# RTLS_Node_sch.net
KiCad netlist of a schematic drawn in Altium Designer
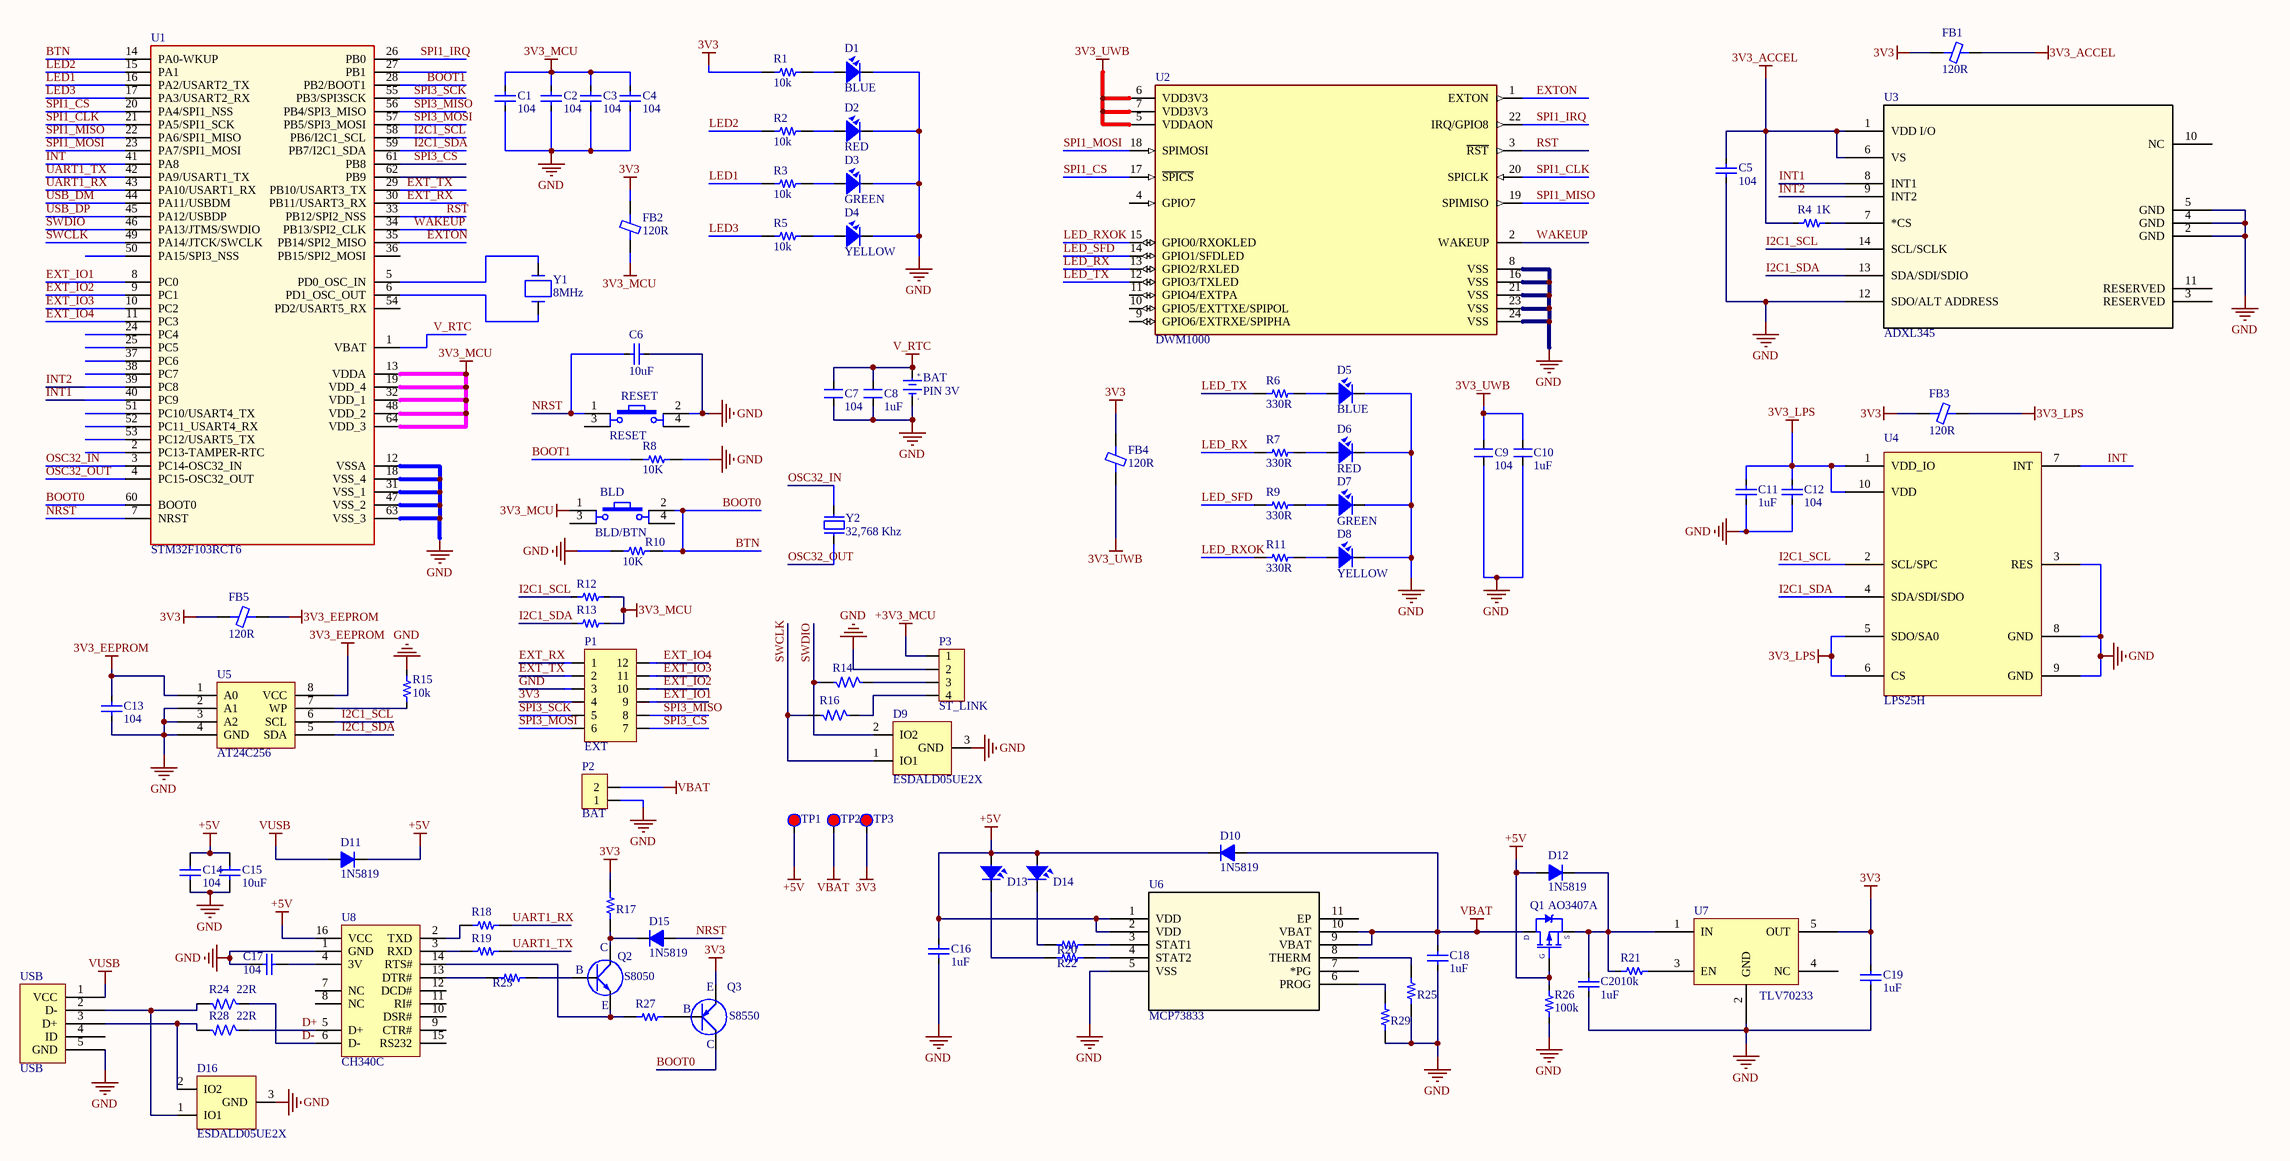
[diagram p0: RTLS_Node_sch.SchDoc]

(export (version "E")
  (design (tool "Eeschema 10.0.6"))
  (components
    (comp (ref "BAT")
      (value "PIN 3V")
      (footprint "CR1220 SMD")
      (description "Battery 3VDC")
      (libsource (lib "My Library") (part "PIN 3V"))
    )
    (comp (ref "BLD")
      (value "BLD/BTN")
      (footprint "SW4 - SMD")
      (description "Switch button 4 pin")
      (libsource (lib "My Library") (part "SW4"))
    )
    (comp (ref "C1")
      (value "104")
      (footprint "CAP_0603")
      (description "Capacitor")
      (fields (field (name "PUBLISHER") "Altium Limited"))
      (libsource (lib "") (part "CapSMD_1"))
    )
    (comp (ref "C2")
      (value "104")
      (footprint "CAP_0603")
      (description "Capacitor")
      (fields (field (name "PUBLISHER") "Altium Limited"))
      (libsource (lib "") (part "CapSMD_1"))
    )
    (comp (ref "C3")
      (value "104")
      (footprint "CAP_0603")
      (description "Capacitor")
      (fields (field (name "PUBLISHER") "Altium Limited"))
      (libsource (lib "") (part "CapSMD_1"))
    )
    (comp (ref "C4")
      (value "104")
      (footprint "CAP_0603")
      (description "Capacitor")
      (fields (field (name "PUBLISHER") "Altium Limited"))
      (libsource (lib "") (part "CapSMD_1"))
    )
    (comp (ref "C5")
      (value "104")
      (footprint "CAP_0603")
      (description "Capacitor")
      (fields (field (name "PUBLISHER") "Altium Limited"))
      (libsource (lib "") (part "CapSMD_1"))
    )
    (comp (ref "C6")
      (value "10uF")
      (footprint "CAP_0603")
      (description "Capacitor")
      (fields (field (name "PUBLISHER") "Altium Limited"))
      (libsource (lib "") (part "CapSMD_1"))
    )
    (comp (ref "C7")
      (value "104")
      (footprint "CAP_0603")
      (description "Cap SMD")
      (libsource (lib "GPS_Traking_V1_1") (part "CM"))
    )
    (comp (ref "C8")
      (value "1uF")
      (footprint "CAP_0603")
      (description "Cap SMD")
      (libsource (lib "GPS_Traking_V1_1") (part "CM"))
    )
    (comp (ref "C9")
      (value "104")
      (footprint "CAP_0603")
      (description "Cap SMD")
      (libsource (lib "GPS_Traking_V1_1") (part "CM"))
    )
    (comp (ref "C10")
      (value "1uF")
      (footprint "CAP_0603")
      (description "Cap SMD")
      (libsource (lib "GPS_Traking_V1_1") (part "CM"))
    )
    (comp (ref "C11")
      (value "1uF")
      (footprint "CAP_0603")
      (description "Capacitor")
      (fields (field (name "PUBLISHER") "Altium Limited"))
      (libsource (lib "") (part "CapSMD_1"))
    )
    (comp (ref "C12")
      (value "104")
      (footprint "CAP_0603")
      (description "Capacitor")
      (fields (field (name "PUBLISHER") "Altium Limited"))
      (libsource (lib "") (part "CapSMD_1"))
    )
    (comp (ref "C13")
      (value "104")
      (footprint "CAP_0603")
      (description "Capacitor")
      (fields (field (name "PUBLISHER") "Altium Limited"))
      (libsource (lib "") (part "CapSMD_1"))
    )
    (comp (ref "C14")
      (value "104")
      (footprint "CAP_0603")
      (description "Capacitor")
      (fields (field (name "PUBLISHER") "Altium Limited"))
      (libsource (lib "My Library") (part "CapSMD"))
    )
    (comp (ref "C15")
      (value "10uF")
      (footprint "CAP_0603")
      (description "Capacitor")
      (fields (field (name "PUBLISHER") "Altium Limited"))
      (libsource (lib "My Library") (part "CapSMD"))
    )
    (comp (ref "C16")
      (value "1uF")
      (footprint "CAP_0603")
      (description "Capacitor")
      (fields (field (name "PUBLISHER") "Altium Limited"))
      (libsource (lib "") (part "CapSMD_1"))
    )
    (comp (ref "C17")
      (value "104")
      (footprint "CAP_0603")
      (description "Capacitor")
      (fields (field (name "PUBLISHER") "Altium Limited"))
      (libsource (lib "My Library") (part "CapSMD"))
    )
    (comp (ref "C18")
      (value "1uF")
      (footprint "CAP_0603")
      (description "Capacitor")
      (fields (field (name "PUBLISHER") "Altium Limited"))
      (libsource (lib "") (part "CapSMD_1"))
    )
    (comp (ref "C19")
      (value "1uF")
      (footprint "CAP_0603")
      (description "Capacitor")
      (fields (field (name "PUBLISHER") "Altium Limited"))
      (libsource (lib "") (part "CapSMD_1"))
    )
    (comp (ref "C20")
      (value "1uF")
      (footprint "CAP_0603")
      (description "Capacitor")
      (fields (field (name "PUBLISHER") "Altium Limited"))
      (libsource (lib "") (part "CapSMD_1"))
    )
    (comp (ref "D1")
      (value "BLUE")
      (footprint "LED-0603-Red")
      (description "LED Single colour Green and Red")
      (libsource (lib "My Library") (part "LED"))
    )
    (comp (ref "D2")
      (value "RED")
      (footprint "LED-0603-Red")
      (description "LED Single colour Green and Red")
      (libsource (lib "My Library") (part "LED"))
    )
    (comp (ref "D3")
      (value "GREEN")
      (footprint "LED-0603-Green")
      (description "LED Single colour Green and Red")
      (libsource (lib "My Library") (part "LED"))
    )
    (comp (ref "D4")
      (value "YELLOW")
      (footprint "LED-0603-Red")
      (description "LED Single colour Green and Red")
      (libsource (lib "My Library") (part "LED"))
    )
    (comp (ref "D5")
      (value "BLUE")
      (footprint "LED-0603-Green")
      (description "LED Single colour Green and Red")
      (libsource (lib "My Library") (part "LED"))
    )
    (comp (ref "D6")
      (value "RED")
      (footprint "LED-0603-Red")
      (description "LED Single colour Green and Red")
      (libsource (lib "My Library") (part "LED"))
    )
    (comp (ref "D7")
      (value "GREEN")
      (footprint "LED-0603-Green")
      (description "LED Single colour Green and Red")
      (libsource (lib "My Library") (part "LED"))
    )
    (comp (ref "D8")
      (value "YELLOW")
      (footprint "LED-0603-Green")
      (description "LED Single colour Green and Red")
      (libsource (lib "My Library") (part "LED"))
    )
    (comp (ref "D9")
      (value "ESDALD05UE2X")
      (footprint "SOT23")
      (libsource (lib "My Library") (part "ESDALD05UE2X"))
    )
    (comp (ref "D10")
      (value "1N5819")
      (footprint "SOD-123")
      (description "Diode 1A")
      (libsource (lib "GPS_Traking_V1_1") (part "D1A_1"))
    )
    (comp (ref "D11")
      (value "1N5819")
      (footprint "SOD-123")
      (description "Diode 1A")
      (libsource (lib "GPS_Traking_V1_1") (part "D1A_1"))
    )
    (comp (ref "D12")
      (value "1N5819")
      (footprint "SOD-123")
      (description "Diode 1A")
      (libsource (lib "GPS_Traking_V1_1") (part "D1A_1"))
    )
    (comp (ref "D13")
      (value "YELLOW")
      (footprint "LED-0603-Red")
      (description "LED Single colour Green and Red")
      (libsource (lib "My Library") (part "LED"))
    )
    (comp (ref "D14")
      (value "YELLOW")
      (footprint "LED-0603-Green")
      (description "LED Single colour Green and Red")
      (libsource (lib "My Library") (part "LED"))
    )
    (comp (ref "D15")
      (value "1N5819")
      (footprint "SOD-123")
      (description "Diode 1A")
      (libsource (lib "GPS_Traking_V1_1") (part "D1A_1"))
    )
    (comp (ref "D16")
      (value "ESDALD05UE2X")
      (footprint "SOT23")
      (libsource (lib "My Library") (part "ESDALD05UE2X"))
    )
    (comp (ref "FB1")
      (value "120R")
      (footprint "RES-SMD-0603")
      (description "Ferrite beads")
      (libsource (lib "My Library") (part "Ferrite beads"))
    )
    (comp (ref "FB2")
      (value "120R")
      (footprint "RES-SMD-0603")
      (description "Ferrite beads")
      (libsource (lib "My Library") (part "Ferrite beads"))
    )
    (comp (ref "FB3")
      (value "120R")
      (footprint "RES-SMD-0603")
      (description "Ferrite beads")
      (libsource (lib "My Library") (part "Ferrite beads"))
    )
    (comp (ref "FB4")
      (value "120R")
      (footprint "RES-SMD-0603")
      (description "Ferrite beads")
      (libsource (lib "My Library") (part "Ferrite beads"))
    )
    (comp (ref "FB5")
      (value "120R")
      (footprint "RES-SMD-0603")
      (description "Ferrite beads")
      (libsource (lib "My Library") (part "Ferrite beads"))
    )
    (comp (ref "P1")
      (value "EXT")
      (footprint "JP6-C2T")
      (description "WR-PHD 2.54 mm Dual Socket Header")
      (fields
        (field (name "MANUFACTURER") "Würth Elektronik eiSos GmbH")
        (field (name "PARTNO") "61301221821")
        (field (name "CREATED BY") "Karrer Zheng")
      )
      (libsource (lib "My Library") (part "JP6x2"))
    )
    (comp (ref "P2")
      (value "BAT")
      (footprint "HEAD2P-1.25")
      (description "Header IDC, 2 x 1 Pin Vertical 2.54mm Pitch (Non-Boxed, Male)")
      (fields
        (field (name "MANUFACTURER") "Würth Elektronik eiSos GmbH")
        (field (name "PARTNO") "613002143121")
        (field (name "CREATED BY") "Karrer Zheng")
      )
      (libsource (lib "My Library") (part "Header2"))
    )
    (comp (ref "P3")
      (value "ST_LINK")
      (footprint "HEADER4P-1.25")
      (description "Header IDC, 4 x 1 Pin Vertical 2.54mm Pitch (Non-Boxed, Male)")
      (fields
        (field (name "MANUFACTURER") "Würth Elektronik eiSos GmbH")
        (field (name "PARTNO") "613002143121")
        (field (name "CREATED BY") "Karrer Zheng")
      )
      (libsource (lib "My Library") (part "Header4"))
    )
    (comp (ref "Q1") (value "AO3407A") (footprint "AO3407A") (libsource (lib "My Library") (part "AO3407A")))
    (comp (ref "Q2") (value "S8050") (footprint "SOT23") (libsource (lib "My Library") (part "S8050")))
    (comp (ref "Q3") (value "S8550") (footprint "SOT23") (libsource (lib "My Library") (part "S8550")))
    (comp (ref "R1")
      (value "10k")
      (footprint "RES-SMD-0603")
      (description "Resistor")
      (fields
        (field (name "MANUFACTURER") "Generic Components")
        (field (name "PUBLISHER") "Altium Hobart Technology Centre")
      )
      (libsource (lib "My Library") (part "Resistor - SMD"))
    )
    (comp (ref "R2")
      (value "10k")
      (footprint "RES-SMD-0603")
      (description "Resistor")
      (fields
        (field (name "MANUFACTURER") "Generic Components")
        (field (name "PUBLISHER") "Altium Hobart Technology Centre")
      )
      (libsource (lib "My Library") (part "Resistor - SMD"))
    )
    (comp (ref "R3")
      (value "10k")
      (footprint "RES-SMD-0603")
      (description "Resistor")
      (fields
        (field (name "MANUFACTURER") "Generic Components")
        (field (name "PUBLISHER") "Altium Hobart Technology Centre")
      )
      (libsource (lib "My Library") (part "Resistor - SMD"))
    )
    (comp (ref "R4")
      (value "1K")
      (footprint "RES-SMD-0603")
      (description "Resistor")
      (fields
        (field (name "MANUFACTURER") "Generic Components")
        (field (name "PUBLISHER") "Altium Hobart Technology Centre")
      )
      (libsource (lib "") (part "Resistor - SMD_1"))
    )
    (comp (ref "R5")
      (value "10k")
      (footprint "RES-SMD-0603")
      (description "Resistor")
      (fields
        (field (name "MANUFACTURER") "Generic Components")
        (field (name "PUBLISHER") "Altium Hobart Technology Centre")
      )
      (libsource (lib "My Library") (part "Resistor - SMD"))
    )
    (comp (ref "R6")
      (value "330R")
      (footprint "RES-SMD-0603")
      (description "Resistor")
      (fields
        (field (name "MANUFACTURER") "Generic Components")
        (field (name "PUBLISHER") "Altium Hobart Technology Centre")
      )
      (libsource (lib "My Library") (part "Resistor - SMD"))
    )
    (comp (ref "R7")
      (value "330R")
      (footprint "RES-SMD-0603")
      (description "Resistor")
      (fields
        (field (name "MANUFACTURER") "Generic Components")
        (field (name "PUBLISHER") "Altium Hobart Technology Centre")
      )
      (libsource (lib "My Library") (part "Resistor - SMD"))
    )
    (comp (ref "R8")
      (value "10K")
      (footprint "RES-SMD-0603")
      (description "Resistor")
      (fields
        (field (name "MANUFACTURER") "Generic Components")
        (field (name "PUBLISHER") "Altium Hobart Technology Centre")
      )
      (libsource (lib "My Library") (part "Resistor - SMD"))
    )
    (comp (ref "R9")
      (value "330R")
      (footprint "RES-SMD-0603")
      (description "Resistor")
      (fields
        (field (name "MANUFACTURER") "Generic Components")
        (field (name "PUBLISHER") "Altium Hobart Technology Centre")
      )
      (libsource (lib "My Library") (part "Resistor - SMD"))
    )
    (comp (ref "R10")
      (value "10K")
      (footprint "RES-SMD-0603")
      (description "Resistor")
      (fields
        (field (name "MANUFACTURER") "Generic Components")
        (field (name "PUBLISHER") "Altium Hobart Technology Centre")
      )
      (libsource (lib "My Library") (part "Resistor - SMD"))
    )
    (comp (ref "R11")
      (value "330R")
      (footprint "RES-SMD-0603")
      (description "Resistor")
      (fields
        (field (name "MANUFACTURER") "Generic Components")
        (field (name "PUBLISHER") "Altium Hobart Technology Centre")
      )
      (libsource (lib "My Library") (part "Resistor - SMD"))
    )
    (comp (ref "R12")
      (value "4.7k")
      (footprint "RES-SMD-0603")
      (description "Resistor")
      (fields
        (field (name "MANUFACTURER") "Generic Components")
        (field (name "PUBLISHER") "Altium Hobart Technology Centre")
      )
      (libsource (lib "") (part "Resistor - SMD_1"))
    )
    (comp (ref "R13")
      (value "4.7k")
      (footprint "RES-SMD-0603")
      (description "Resistor")
      (fields
        (field (name "MANUFACTURER") "Generic Components")
        (field (name "PUBLISHER") "Altium Hobart Technology Centre")
      )
      (libsource (lib "") (part "Resistor - SMD_1"))
    )
    (comp (ref "R14")
      (value "10R")
      (footprint "RES-SMD-0603")
      (description "Resistor SMD")
      (libsource (lib "GPS_Traking_V1_1") (part "RM"))
    )
    (comp (ref "R15")
      (value "10k")
      (footprint "RES-SMD-0603")
      (description "Resistor")
      (fields
        (field (name "MANUFACTURER") "Generic Components")
        (field (name "PUBLISHER") "Altium Hobart Technology Centre")
      )
      (libsource (lib "") (part "Resistor - SMD_1"))
    )
    (comp (ref "R16")
      (value "10R")
      (footprint "RES-SMD-0603")
      (description "Resistor SMD")
      (libsource (lib "GPS_Traking_V1_1") (part "RM"))
    )
    (comp (ref "R17")
      (value "1K")
      (footprint "RES-SMD-0603")
      (description "Resistor")
      (fields
        (field (name "MANUFACTURER") "Generic Components")
        (field (name "PUBLISHER") "Altium Hobart Technology Centre")
      )
      (libsource (lib "My Library") (part "Resistor - SMD"))
    )
    (comp (ref "R18")
      (value "1K")
      (footprint "RES-SMD-0603")
      (description "Resistor")
      (fields
        (field (name "MANUFACTURER") "Generic Components")
        (field (name "PUBLISHER") "Altium Hobart Technology Centre")
      )
      (libsource (lib "My Library") (part "Resistor - SMD"))
    )
    (comp (ref "R19")
      (value "1K")
      (footprint "RES-SMD-0603")
      (description "Resistor")
      (fields
        (field (name "MANUFACTURER") "Generic Components")
        (field (name "PUBLISHER") "Altium Hobart Technology Centre")
      )
      (libsource (lib "My Library") (part "Resistor - SMD"))
    )
    (comp (ref "R20")
      (value "10k")
      (footprint "RES-SMD-0603")
      (description "Resistor")
      (fields
        (field (name "MANUFACTURER") "Generic Components")
        (field (name "PUBLISHER") "Altium Hobart Technology Centre")
      )
      (libsource (lib "My Library") (part "Resistor - SMD"))
    )
    (comp (ref "R21")
      (value "10k")
      (footprint "RES-SMD-0603")
      (description "Resistor")
      (fields
        (field (name "MANUFACTURER") "Generic Components")
        (field (name "PUBLISHER") "Altium Hobart Technology Centre")
      )
      (libsource (lib "") (part "Resistor - SMD_1"))
    )
    (comp (ref "R22")
      (value "10k")
      (footprint "RES-SMD-0603")
      (description "Resistor")
      (fields
        (field (name "MANUFACTURER") "Generic Components")
        (field (name "PUBLISHER") "Altium Hobart Technology Centre")
      )
      (libsource (lib "My Library") (part "Resistor - SMD"))
    )
    (comp (ref "R23")
      (value "1K")
      (footprint "RES-SMD-0603")
      (description "Resistor")
      (fields
        (field (name "MANUFACTURER") "Generic Components")
        (field (name "PUBLISHER") "Altium Hobart Technology Centre")
      )
      (libsource (lib "My Library") (part "Resistor - SMD"))
    )
    (comp (ref "R24")
      (value "22R")
      (footprint "RES-SMD-0603")
      (description "Resistor SMD")
      (libsource (lib "GPS_Traking_V1_1") (part "RM"))
    )
    (comp (ref "R25")
      (value "10k")
      (footprint "RES-SMD-0603")
      (description "Resistor")
      (fields
        (field (name "MANUFACTURER") "Generic Components")
        (field (name "PUBLISHER") "Altium Hobart Technology Centre")
      )
      (libsource (lib "My Library") (part "Resistor - SMD"))
    )
    (comp (ref "R26")
      (value "100k")
      (footprint "RES-SMD-0603")
      (description "Resistor")
      (fields
        (field (name "MANUFACTURER") "Generic Components")
        (field (name "PUBLISHER") "Altium Hobart Technology Centre")
      )
      (libsource (lib "") (part "Resistor - SMD_1"))
    )
    (comp (ref "R27")
      (value "1K")
      (footprint "RES-SMD-0603")
      (description "Resistor")
      (fields
        (field (name "MANUFACTURER") "Generic Components")
        (field (name "PUBLISHER") "Altium Hobart Technology Centre")
      )
      (libsource (lib "My Library") (part "Resistor - SMD"))
    )
    (comp (ref "R28")
      (value "22R")
      (footprint "RES-SMD-0603")
      (description "Resistor SMD")
      (libsource (lib "GPS_Traking_V1_1") (part "RM"))
    )
    (comp (ref "R29")
      (value "1k")
      (footprint "RES-SMD-0603")
      (description "Resistor")
      (fields
        (field (name "MANUFACTURER") "Generic Components")
        (field (name "PUBLISHER") "Altium Hobart Technology Centre")
      )
      (libsource (lib "My Library") (part "Resistor - SMD"))
    )
    (comp (ref "RESET")
      (value "RESET")
      (footprint "SW4 - SMD")
      (description "Switch button 4 pin")
      (libsource (lib "My Library") (part "SW4"))
    )
    (comp (ref "TP1") (value "Testpoint") (footprint "TP1") (libsource (lib "My Library") (part "Testpoint")))
    (comp (ref "TP2") (value "Testpoint") (footprint "TP1") (libsource (lib "My Library") (part "Testpoint")))
    (comp (ref "TP3") (value "Testpoint") (footprint "TP1") (libsource (lib "My Library") (part "Testpoint")))
    (comp (ref "U1")
      (value "STM32F103RCT6")
      (footprint "STM32F103RCT6")
      (description "STM32F103RCT6 32Bit MCU")
      (libsource (lib "My Library") (part "STM32F103RCT6"))
    )
    (comp (ref "U2")
      (value "DWM1000")
      (footprint "DW1000")
      (description "Decawave's DW1000 Ultra\r\nWideband (UWB) transceiver IC")
      (libsource (lib "My Library") (part "DWM1000"))
    )
    (comp (ref "U3")
      (value "ADXL345")
      (footprint "ADXL345")
      (description "3 Axis Digital Accelerometer")
      (libsource (lib "My Library") (part "ADXL345"))
    )
    (comp (ref "U4") (value "LPS25H") (footprint "LPS25H") (libsource (lib "My Library") (part "LPS25H")))
    (comp (ref "U5") (value "AT24C256") (footprint "SOIC-8") (libsource (lib "My Library") (part "AT24C256")))
    (comp (ref "U6")
      (value "MCP73833")
      (footprint "MCP73833")
      (libsource (lib "My Library") (part "MCP73833"))
    )
    (comp (ref "U7")
      (value "TLV70223")
      (footprint "SOT23-5")
      (fields (field (name "NAME") "TLV70233"))
      (libsource (lib "My Library") (part "TLV70223"))
    )
    (comp (ref "U8") (value "CH340C") (footprint "SO16") (libsource (lib "My Library") (part "CH340C")))
    (comp (ref "USB") (value "USB") (footprint "Micro Usb") (libsource (lib "My Library") (part "USB_1")))
    (comp (ref "Y1")
      (value "8MHz")
      (footprint "ABM7_v1_1_BIG")
      (description "CRYSTAL 16MHZ 18PF SMD")
      (fields
        (field (name "MANUFACTURER") "Abracon LLC")
        (field (name "MANUFACTURER PART NUMBER") "ABM7-16.000MHZ-D2Y-T")
        (field (name ".CREATOR") "MM")
        (field (name ".CHECKED PCB") "RF")
        (field (name ".CHECKED SCH") "RF")
      )
      (libsource (lib "GPS_Traking_V1_1") (part "ABM7-16.000MHZ-D2Y-T"))
    )
    (comp (ref "Y2")
      (value "32,768 Khz")
      (footprint "FC135 32.768")
      (description "Crystal 32,768kHz for timer real")
      (libsource (lib "DATN_Lib") (part "XT32k"))
    )
  )
  (nets
    (net (code "1") (name "+3V3_MCU") (class "Default")
      (node (ref "P3") (pin "1") (pinfunction "1_1") (pintype "passive"))
    )
    (net (code "2") (name "+5V") (class "Default")
      (node (ref "C14") (pin "2") (pinfunction "2_2") (pintype "passive"))
      (node (ref "C15") (pin "2") (pinfunction "2_2") (pintype "passive"))
      (node (ref "C16") (pin "1") (pinfunction "1_1") (pintype "passive"))
      (node (ref "D10") (pin "2") (pinfunction "K_2") (pintype "passive"))
      (node (ref "D11") (pin "2") (pinfunction "K_2") (pintype "passive"))
      (node (ref "D12") (pin "1") (pinfunction "A_1") (pintype "passive"))
      (node (ref "D13") (pin "1") (pinfunction "1_1") (pintype "passive"))
      (node (ref "D14") (pin "1") (pinfunction "1_1") (pintype "passive"))
      (node (ref "Q1") (pin "1") (pinfunction "G_1") (pintype "passive"))
      (node (ref "R26") (pin "2") (pinfunction "2_2") (pintype "passive"))
      (node (ref "TP1") (pin "1") (pinfunction "1_1") (pintype "passive"))
      (node (ref "U6") (pin "1") (pinfunction "VDD_1") (pintype "passive"))
      (node (ref "U6") (pin "2") (pinfunction "VDD_2") (pintype "passive"))
      (node (ref "U8") (pin "16") (pinfunction "VCC_16") (pintype "passive"))
    )
    (net (code "3") (name "/BOOT0") (class "Default")
      (node (ref "BLD") (pin "2") (pintype "passive"))
      (node (ref "Q3") (pin "3") (pinfunction "C_3") (pintype "passive"))
      (node (ref "R10") (pin "2") (pinfunction "2_2") (pintype "passive"))
      (node (ref "U1") (pin "14") (pinfunction "PA0-WKUP_14") (pintype "passive"))
      (node (ref "U1") (pin "60") (pinfunction "BOOT0_60") (pintype "passive"))
    )
    (net (code "4") (name "/BOOT1") (class "Default")
      (node (ref "R8") (pin "1") (pinfunction "1_1") (pintype "passive"))
      (node (ref "U1") (pin "28") (pinfunction "PB2/BOOT1_28") (pintype "passive"))
    )
    (net (code "5") (name "/D+") (class "Default")
      (node (ref "R28") (pin "1") (pinfunction "1_1") (pintype "passive"))
      (node (ref "U8") (pin "5") (pinfunction "D+_5") (pintype "passive"))
    )
    (net (code "6") (name "/D-") (class "Default")
      (node (ref "R24") (pin "1") (pinfunction "1_1") (pintype "passive"))
      (node (ref "U8") (pin "6") (pinfunction "D-_6") (pintype "passive"))
    )
    (net (code "7") (name "/EXTON") (class "Default")
      (node (ref "U1") (pin "35") (pinfunction "PB14/SPI2_MISO_35") (pintype "passive"))
      (node (ref "U2") (pin "1") (pinfunction "EXTON_1") (pintype "output"))
    )
    (net (code "8") (name "/EXT_IO1") (class "Default")
      (node (ref "P1") (pin "9") (pinfunction "9_9") (pintype "passive"))
      (node (ref "U1") (pin "8") (pinfunction "PC0_8") (pintype "passive"))
    )
    (net (code "9") (name "/EXT_IO2") (class "Default")
      (node (ref "P1") (pin "10") (pinfunction "10_10") (pintype "passive"))
      (node (ref "U1") (pin "9") (pinfunction "PC1_9") (pintype "passive"))
    )
    (net (code "10") (name "/EXT_IO3") (class "Default")
      (node (ref "P1") (pin "11") (pinfunction "11_11") (pintype "passive"))
      (node (ref "U1") (pin "10") (pinfunction "PC2_10") (pintype "passive"))
    )
    (net (code "11") (name "/EXT_IO4") (class "Default")
      (node (ref "P1") (pin "12") (pinfunction "12_12") (pintype "passive"))
      (node (ref "U1") (pin "11") (pinfunction "PC3_11") (pintype "passive"))
    )
    (net (code "12") (name "/EXT_RX") (class "Default")
      (node (ref "P1") (pin "1") (pinfunction "1_1") (pintype "passive"))
      (node (ref "U1") (pin "30") (pinfunction "PB11/USART3_RX_30") (pintype "passive"))
    )
    (net (code "13") (name "/EXT_TX") (class "Default")
      (node (ref "P1") (pin "2") (pinfunction "2_2") (pintype "passive"))
      (node (ref "U1") (pin "29") (pinfunction "PB10/USART3_TX_29") (pintype "passive"))
    )
    (net (code "14") (name "/I2C1_SCL") (class "Default")
      (node (ref "R12") (pin "2") (pinfunction "2_2") (pintype "passive"))
      (node (ref "U1") (pin "58") (pinfunction "PB6/I2C1_SCL_58") (pintype "passive"))
      (node (ref "U3") (pin "14") (pinfunction "SCL/SCLK_14") (pintype "passive"))
      (node (ref "U4") (pin "2") (pinfunction "SCL/SPC_2") (pintype "passive"))
      (node (ref "U5") (pin "6") (pinfunction "SCL_6") (pintype "passive"))
    )
    (net (code "15") (name "/I2C1_SDA") (class "Default")
      (node (ref "R13") (pin "2") (pinfunction "2_2") (pintype "passive"))
      (node (ref "U1") (pin "59") (pinfunction "PB7/I2C1_SDA_59") (pintype "passive"))
      (node (ref "U3") (pin "13") (pinfunction "SDA/SDI/SDIO_13") (pintype "passive"))
      (node (ref "U4") (pin "4") (pinfunction "SDA/SDI/SDO_4") (pintype "passive"))
      (node (ref "U5") (pin "5") (pinfunction "SDA_5") (pintype "passive"))
    )
    (net (code "16") (name "/INT") (class "Default")
      (node (ref "U1") (pin "41") (pinfunction "PA8_41") (pintype "passive"))
      (node (ref "U4") (pin "7") (pinfunction "INT_7") (pintype "passive"))
    )
    (net (code "17") (name "/INT1") (class "Default")
      (node (ref "U1") (pin "40") (pinfunction "PC9_40") (pintype "passive"))
      (node (ref "U3") (pin "8") (pinfunction "INT1_8") (pintype "passive"))
    )
    (net (code "18") (name "/INT2") (class "Default")
      (node (ref "U1") (pin "39") (pinfunction "PC8_39") (pintype "passive"))
      (node (ref "U3") (pin "9") (pinfunction "INT2_9") (pintype "passive"))
    )
    (net (code "19") (name "/LED1") (class "Default")
      (node (ref "R3") (pin "2") (pinfunction "2_2") (pintype "passive"))
      (node (ref "U1") (pin "16") (pinfunction "PA2/USART2_TX_16") (pintype "passive"))
    )
    (net (code "20") (name "/LED2") (class "Default")
      (node (ref "R2") (pin "2") (pinfunction "2_2") (pintype "passive"))
      (node (ref "U1") (pin "15") (pinfunction "PA1_15") (pintype "passive"))
    )
    (net (code "21") (name "/LED3") (class "Default")
      (node (ref "R5") (pin "2") (pinfunction "2_2") (pintype "passive"))
      (node (ref "U1") (pin "17") (pinfunction "PA3/USART2_RX_17") (pintype "passive"))
    )
    (net (code "22") (name "/LED_RX") (class "Default")
      (node (ref "R7") (pin "2") (pinfunction "2_2") (pintype "passive"))
      (node (ref "U2") (pin "13") (pinfunction "GPIO2/RXLED_13") (pintype "bidirectional"))
    )
    (net (code "23") (name "/LED_RXOK") (class "Default")
      (node (ref "R11") (pin "2") (pinfunction "2_2") (pintype "passive"))
      (node (ref "U2") (pin "15") (pinfunction "GPIO0/RXOKLED_15") (pintype "bidirectional"))
    )
    (net (code "24") (name "/LED_SFD") (class "Default")
      (node (ref "R9") (pin "2") (pinfunction "2_2") (pintype "passive"))
      (node (ref "U2") (pin "14") (pinfunction "GPIO1/SFDLED_14") (pintype "bidirectional"))
    )
    (net (code "25") (name "/LED_TX") (class "Default")
      (node (ref "R6") (pin "2") (pinfunction "2_2") (pintype "passive"))
      (node (ref "U2") (pin "12") (pinfunction "GPIO3/TXLED_12") (pintype "bidirectional"))
    )
    (net (code "26") (name "/NRST") (class "Default")
      (node (ref "C6") (pin "2") (pinfunction "2_2") (pintype "passive"))
      (node (ref "D15") (pin "1") (pinfunction "A_1") (pintype "passive"))
      (node (ref "RESET") (pin "1") (pintype "passive"))
      (node (ref "U1") (pin "7") (pinfunction "NRST_7") (pintype "passive"))
    )
    (net (code "27") (name "/OSC32_IN") (class "Default")
      (node (ref "U1") (pin "3") (pinfunction "PC14-OSC32_IN_3") (pintype "passive"))
      (node (ref "Y2") (pin "2") (pinfunction "2_2") (pintype "passive"))
    )
    (net (code "28") (name "/OSC32_OUT") (class "Default")
      (node (ref "U1") (pin "4") (pinfunction "PC15-OSC32_OUT_4") (pintype "passive"))
      (node (ref "Y2") (pin "1") (pinfunction "1_1") (pintype "passive"))
    )
    (net (code "29") (name "/RST") (class "Default")
      (node (ref "U1") (pin "33") (pinfunction "PB12/SPI2_NSS_33") (pintype "passive"))
      (node (ref "U2") (pin "3") (pinfunction "~{RST}_3") (pintype "output"))
    )
    (net (code "30") (name "/SPI1_CLK") (class "Default")
      (node (ref "U1") (pin "21") (pinfunction "PA5/SPI1_SCK_21") (pintype "passive"))
      (node (ref "U2") (pin "20") (pinfunction "SPICLK_20") (pintype "input"))
    )
    (net (code "31") (name "/SPI1_CS") (class "Default")
      (node (ref "U1") (pin "20") (pinfunction "PA4/SPI1_NSS_20") (pintype "passive"))
      (node (ref "U2") (pin "17") (pinfunction "~{SPICS}_17") (pintype "input"))
    )
    (net (code "32") (name "/SPI1_IRQ") (class "Default")
      (node (ref "U1") (pin "26") (pinfunction "PB0_26") (pintype "passive"))
      (node (ref "U2") (pin "22") (pinfunction "IRQ/GPIO8_22") (pintype "output"))
    )
    (net (code "33") (name "/SPI1_MISO") (class "Default")
      (node (ref "U1") (pin "22") (pinfunction "PA6/SPI1_MISO_22") (pintype "passive"))
      (node (ref "U2") (pin "19") (pinfunction "SPIMISO_19") (pintype "output"))
    )
    (net (code "34") (name "/SPI1_MOSI") (class "Default")
      (node (ref "U1") (pin "23") (pinfunction "PA7/SPI1_MOSI_23") (pintype "passive"))
      (node (ref "U2") (pin "18") (pinfunction "SPIMOSI_18") (pintype "input"))
    )
    (net (code "35") (name "/SPI3_CS") (class "Default")
      (node (ref "P1") (pin "7") (pinfunction "7_7") (pintype "passive"))
      (node (ref "U1") (pin "61") (pinfunction "PB8_61") (pintype "passive"))
    )
    (net (code "36") (name "/SPI3_MISO") (class "Default")
      (node (ref "P1") (pin "8") (pinfunction "8_8") (pintype "passive"))
      (node (ref "U1") (pin "56") (pinfunction "PB4/SPI3_MISO_56") (pintype "passive"))
    )
    (net (code "37") (name "/SPI3_MOSI") (class "Default")
      (node (ref "P1") (pin "6") (pinfunction "6_6") (pintype "passive"))
      (node (ref "U1") (pin "57") (pinfunction "PB5/SPI3_MOSI_57") (pintype "passive"))
    )
    (net (code "38") (name "/SPI3_SCK") (class "Default")
      (node (ref "P1") (pin "5") (pinfunction "5_5") (pintype "passive"))
      (node (ref "U1") (pin "55") (pinfunction "PB3/SPI3SCK_55") (pintype "passive"))
    )
    (net (code "39") (name "/SWCLK") (class "Default")
      (node (ref "D9") (pin "1") (pinfunction "IO1_1") (pintype "passive"))
      (node (ref "R16") (pin "2") (pinfunction "2_2") (pintype "passive"))
      (node (ref "U1") (pin "49") (pinfunction "PA14/JTCK/SWCLK_49") (pintype "passive"))
    )
    (net (code "40") (name "/SWDIO") (class "Default")
      (node (ref "D9") (pin "2") (pinfunction "IO2_2") (pintype "passive"))
      (node (ref "R14") (pin "2") (pinfunction "2_2") (pintype "passive"))
      (node (ref "U1") (pin "46") (pinfunction "PA13/JTMS/SWDIO_46") (pintype "passive"))
    )
    (net (code "41") (name "/UART1_RX") (class "Default")
      (node (ref "R18") (pin "2") (pinfunction "2_2") (pintype "passive"))
      (node (ref "U1") (pin "43") (pinfunction "PA10/USART1_RX_43") (pintype "passive"))
    )
    (net (code "42") (name "/UART1_TX") (class "Default")
      (node (ref "R19") (pin "2") (pinfunction "2_2") (pintype "passive"))
      (node (ref "U1") (pin "42") (pinfunction "PA9/USART1_TX_42") (pintype "passive"))
    )
    (net (code "43") (name "/USB_DM") (class "Default")
      (node (ref "U1") (pin "44") (pinfunction "PA11/USBDM_44") (pintype "passive"))
    )
    (net (code "44") (name "/USB_DP") (class "Default")
      (node (ref "U1") (pin "45") (pinfunction "PA12/USBDP_45") (pintype "passive"))
    )
    (net (code "45") (name "/WAKEUP") (class "Default")
      (node (ref "U1") (pin "34") (pinfunction "PB13/SPI2_CLK_34") (pintype "passive"))
      (node (ref "U2") (pin "2") (pinfunction "WAKEUP_2") (pintype "passive"))
    )
    (net (code "46") (name "3V3") (class "Default")
      (node (ref "C19") (pin "1") (pinfunction "1_1") (pintype "passive"))
      (node (ref "FB1") (pin "1") (pinfunction "1_1") (pintype "passive"))
      (node (ref "FB2") (pin "2") (pinfunction "2_2") (pintype "passive"))
      (node (ref "FB3") (pin "1") (pinfunction "1_1") (pintype "passive"))
      (node (ref "FB4") (pin "1") (pinfunction "1_1") (pintype "passive"))
      (node (ref "FB5") (pin "1") (pinfunction "1_1") (pintype "passive"))
      (node (ref "P1") (pin "4") (pinfunction "4_4") (pintype "passive"))
      (node (ref "Q3") (pin "2") (pinfunction "E_2") (pintype "passive"))
      (node (ref "R1") (pin "2") (pinfunction "2_2") (pintype "passive"))
      (node (ref "R17") (pin "2") (pinfunction "2_2") (pintype "passive"))
      (node (ref "TP3") (pin "1") (pinfunction "1_1") (pintype "passive"))
      (node (ref "U7") (pin "5") (pinfunction "OUT_5") (pintype "passive"))
    )
    (net (code "47") (name "3V3_ACCEL") (class "Default")
      (node (ref "C5") (pin "1") (pinfunction "1_1") (pintype "passive"))
      (node (ref "FB1") (pin "2") (pinfunction "2_2") (pintype "passive"))
      (node (ref "R4") (pin "2") (pinfunction "2_2") (pintype "passive"))
      (node (ref "U3") (pin "1") (pinfunction "VDD_I/O_1") (pintype "passive"))
      (node (ref "U3") (pin "6") (pinfunction "VS_6") (pintype "passive"))
    )
    (net (code "48") (name "3V3_EEPROM") (class "Default")
      (node (ref "C13") (pin "1") (pinfunction "1_1") (pintype "passive"))
      (node (ref "FB5") (pin "2") (pinfunction "2_2") (pintype "passive"))
      (node (ref "U5") (pin "1") (pinfunction "A0_1") (pintype "passive"))
      (node (ref "U5") (pin "8") (pinfunction "VCC_8") (pintype "passive"))
    )
    (net (code "49") (name "3V3_LPS") (class "Default")
      (node (ref "C11") (pin "1") (pinfunction "1_1") (pintype "passive"))
      (node (ref "C12") (pin "1") (pinfunction "1_1") (pintype "passive"))
      (node (ref "FB3") (pin "2") (pinfunction "2_2") (pintype "passive"))
      (node (ref "U4") (pin "1") (pinfunction "VDD_IO_1") (pintype "passive"))
      (node (ref "U4") (pin "10") (pinfunction "VDD_10") (pintype "passive"))
      (node (ref "U4") (pin "5") (pinfunction "SDO/SA0_5") (pintype "passive"))
      (node (ref "U4") (pin "6") (pinfunction "CS_6") (pintype "passive"))
    )
    (net (code "50") (name "3V3_MCU") (class "Default")
      (node (ref "BLD") (pin "1") (pintype "passive"))
      (node (ref "C1") (pin "2") (pinfunction "2_2") (pintype "passive"))
      (node (ref "C2") (pin "2") (pinfunction "2_2") (pintype "passive"))
      (node (ref "C3") (pin "2") (pinfunction "2_2") (pintype "passive"))
      (node (ref "C4") (pin "2") (pinfunction "2_2") (pintype "passive"))
      (node (ref "FB2") (pin "1") (pinfunction "1_1") (pintype "passive"))
      (node (ref "R12") (pin "1") (pinfunction "1_1") (pintype "passive"))
      (node (ref "R13") (pin "1") (pinfunction "1_1") (pintype "passive"))
      (node (ref "U1") (pin "13") (pinfunction "VDDA_13") (pintype "passive"))
      (node (ref "U1") (pin "19") (pinfunction "VDD_4_19") (pintype "passive"))
      (node (ref "U1") (pin "32") (pinfunction "VDD_1_32") (pintype "passive"))
      (node (ref "U1") (pin "48") (pinfunction "VDD_2_48") (pintype "passive"))
      (node (ref "U1") (pin "64") (pinfunction "VDD_3_64") (pintype "passive"))
    )
    (net (code "51") (name "3V3_UWB") (class "Default")
      (node (ref "C10") (pin "2") (pinfunction "2_2") (pintype "passive"))
      (node (ref "C9") (pin "2") (pinfunction "2_2") (pintype "passive"))
      (node (ref "FB4") (pin "2") (pinfunction "2_2") (pintype "passive"))
      (node (ref "U2") (pin "5") (pinfunction "VDDAON_5") (pintype "power_in"))
      (node (ref "U2") (pin "6") (pinfunction "VDD3V3_6") (pintype "power_in"))
      (node (ref "U2") (pin "7") (pinfunction "VDD3V3_7") (pintype "power_in"))
    )
    (net (code "52") (name "GND") (class "Default")
      (node (ref "BAT") (pin "2") (pinfunction "GND_2") (pintype "passive"))
      (node (ref "C1") (pin "1") (pinfunction "1_1") (pintype "passive"))
      (node (ref "C10") (pin "1") (pinfunction "1_1") (pintype "passive"))
      (node (ref "C11") (pin "2") (pinfunction "2_2") (pintype "passive"))
      (node (ref "C12") (pin "2") (pinfunction "2_2") (pintype "passive"))
      (node (ref "C13") (pin "2") (pinfunction "2_2") (pintype "passive"))
      (node (ref "C14") (pin "1") (pinfunction "1_1") (pintype "passive"))
      (node (ref "C15") (pin "1") (pinfunction "1_1") (pintype "passive"))
      (node (ref "C16") (pin "2") (pinfunction "2_2") (pintype "passive"))
      (node (ref "C17") (pin "1") (pinfunction "1_1") (pintype "passive"))
      (node (ref "C18") (pin "2") (pinfunction "2_2") (pintype "passive"))
      (node (ref "C19") (pin "2") (pinfunction "2_2") (pintype "passive"))
      (node (ref "C2") (pin "1") (pinfunction "1_1") (pintype "passive"))
      (node (ref "C20") (pin "2") (pinfunction "2_2") (pintype "passive"))
      (node (ref "C3") (pin "1") (pinfunction "1_1") (pintype "passive"))
      (node (ref "C4") (pin "1") (pinfunction "1_1") (pintype "passive"))
      (node (ref "C5") (pin "2") (pinfunction "2_2") (pintype "passive"))
      (node (ref "C6") (pin "1") (pinfunction "1_1") (pintype "passive"))
      (node (ref "C7") (pin "1") (pinfunction "1_1") (pintype "passive"))
      (node (ref "C8") (pin "1") (pinfunction "1_1") (pintype "passive"))
      (node (ref "C9") (pin "1") (pinfunction "1_1") (pintype "passive"))
      (node (ref "D1") (pin "2") (pinfunction "2_2") (pintype "passive"))
      (node (ref "D16") (pin "3") (pinfunction "GND_3") (pintype "passive"))
      (node (ref "D2") (pin "2") (pinfunction "2_2") (pintype "passive"))
      (node (ref "D3") (pin "2") (pinfunction "2_2") (pintype "passive"))
      (node (ref "D4") (pin "2") (pinfunction "2_2") (pintype "passive"))
      (node (ref "D5") (pin "2") (pinfunction "2_2") (pintype "passive"))
      (node (ref "D6") (pin "2") (pinfunction "2_2") (pintype "passive"))
      (node (ref "D7") (pin "2") (pinfunction "2_2") (pintype "passive"))
      (node (ref "D8") (pin "2") (pinfunction "2_2") (pintype "passive"))
      (node (ref "D9") (pin "3") (pinfunction "GND_3") (pintype "passive"))
      (node (ref "P1") (pin "3") (pinfunction "3_3") (pintype "passive"))
      (node (ref "P2") (pin "1") (pinfunction "1_1") (pintype "passive"))
      (node (ref "P3") (pin "2") (pinfunction "2_2") (pintype "passive"))
      (node (ref "R10") (pin "1") (pinfunction "1_1") (pintype "passive"))
      (node (ref "R15") (pin "2") (pinfunction "2_2") (pintype "passive"))
      (node (ref "R25") (pin "2") (pinfunction "2_2") (pintype "passive"))
      (node (ref "R26") (pin "1") (pinfunction "1_1") (pintype "passive"))
      (node (ref "R29") (pin "2") (pinfunction "2_2") (pintype "passive"))
      (node (ref "R8") (pin "2") (pinfunction "2_2") (pintype "passive"))
      (node (ref "RESET") (pin "2") (pintype "passive"))
      (node (ref "U1") (pin "12") (pinfunction "VSSA_12") (pintype "passive"))
      (node (ref "U1") (pin "18") (pinfunction "VSS_4_18") (pintype "passive"))
      (node (ref "U1") (pin "31") (pinfunction "VSS_1_31") (pintype "passive"))
      (node (ref "U1") (pin "47") (pinfunction "VSS_2_47") (pintype "passive"))
      (node (ref "U1") (pin "63") (pinfunction "VSS_3_63") (pintype "passive"))
      (node (ref "U2") (pin "16") (pinfunction "VSS_16") (pintype "power_in"))
      (node (ref "U2") (pin "21") (pinfunction "VSS_21") (pintype "power_in"))
      (node (ref "U2") (pin "23") (pinfunction "VSS_23") (pintype "power_in"))
      (node (ref "U2") (pin "24") (pinfunction "VSS_24") (pintype "power_in"))
      (node (ref "U2") (pin "8") (pinfunction "VSS_8") (pintype "power_in"))
      (node (ref "U3") (pin "12") (pinfunction "SDO/ALT_ADDRESS_12") (pintype "passive"))
      (node (ref "U3") (pin "2") (pinfunction "GND_2") (pintype "passive"))
      (node (ref "U3") (pin "4") (pinfunction "GND_4") (pintype "passive"))
      (node (ref "U3") (pin "5") (pinfunction "GND_5") (pintype "passive"))
      (node (ref "U4") (pin "3") (pinfunction "RES_3") (pintype "passive"))
      (node (ref "U4") (pin "8") (pinfunction "GND_8") (pintype "passive"))
      (node (ref "U4") (pin "9") (pinfunction "GND_9") (pintype "passive"))
      (node (ref "U5") (pin "2") (pinfunction "A1_2") (pintype "passive"))
      (node (ref "U5") (pin "3") (pinfunction "A2_3") (pintype "passive"))
      (node (ref "U5") (pin "4") (pinfunction "GND_4") (pintype "passive"))
      (node (ref "U6") (pin "5") (pinfunction "VSS_5") (pintype "passive"))
      (node (ref "U7") (pin "2") (pinfunction "GND_2") (pintype "passive"))
      (node (ref "U8") (pin "1") (pinfunction "GND_1") (pintype "passive"))
      (node (ref "USB") (pin "5") (pinfunction "GND_5") (pintype "passive"))
    )
    (net (code "53") (name "Net-(D1-Pad1)") (class "Default")
      (node (ref "D1") (pin "1") (pinfunction "1_1") (pintype "passive"))
      (node (ref "R1") (pin "1") (pinfunction "1_1") (pintype "passive"))
    )
    (net (code "54") (name "Net-(D2-Pad1)") (class "Default")
      (node (ref "D2") (pin "1") (pinfunction "1_1") (pintype "passive"))
      (node (ref "R2") (pin "1") (pinfunction "1_1") (pintype "passive"))
    )
    (net (code "55") (name "Net-(D3-Pad1)") (class "Default")
      (node (ref "D3") (pin "1") (pinfunction "1_1") (pintype "passive"))
      (node (ref "R3") (pin "1") (pinfunction "1_1") (pintype "passive"))
    )
    (net (code "56") (name "Net-(D4-Pad1)") (class "Default")
      (node (ref "D4") (pin "1") (pinfunction "1_1") (pintype "passive"))
      (node (ref "R5") (pin "1") (pinfunction "1_1") (pintype "passive"))
    )
    (net (code "57") (name "Net-(D5-Pad1)") (class "Default")
      (node (ref "D5") (pin "1") (pinfunction "1_1") (pintype "passive"))
      (node (ref "R6") (pin "1") (pinfunction "1_1") (pintype "passive"))
    )
    (net (code "58") (name "Net-(D6-Pad1)") (class "Default")
      (node (ref "D6") (pin "1") (pinfunction "1_1") (pintype "passive"))
      (node (ref "R7") (pin "1") (pinfunction "1_1") (pintype "passive"))
    )
    (net (code "59") (name "Net-(D7-Pad1)") (class "Default")
      (node (ref "D7") (pin "1") (pinfunction "1_1") (pintype "passive"))
      (node (ref "R9") (pin "1") (pinfunction "1_1") (pintype "passive"))
    )
    (net (code "60") (name "Net-(D8-Pad1)") (class "Default")
      (node (ref "D8") (pin "1") (pinfunction "1_1") (pintype "passive"))
      (node (ref "R11") (pin "1") (pinfunction "1_1") (pintype "passive"))
    )
    (net (code "61") (name "Net-(D12-K)") (class "Default")
      (node (ref "C20") (pin "1") (pinfunction "1_1") (pintype "passive"))
      (node (ref "D12") (pin "2") (pinfunction "K_2") (pintype "passive"))
      (node (ref "Q1") (pin "2") (pinfunction "S_2") (pintype "passive"))
      (node (ref "R21") (pin "2") (pinfunction "2_2") (pintype "passive"))
      (node (ref "U7") (pin "1") (pinfunction "IN_1") (pintype "passive"))
    )
    (net (code "62") (name "Net-(D13-Pad2)") (class "Default")
      (node (ref "D13") (pin "2") (pinfunction "2_2") (pintype "passive"))
      (node (ref "R22") (pin "2") (pinfunction "2_2") (pintype "passive"))
    )
    (net (code "63") (name "Net-(D14-Pad2)") (class "Default")
      (node (ref "D14") (pin "2") (pinfunction "2_2") (pintype "passive"))
      (node (ref "R20") (pin "2") (pinfunction "2_2") (pintype "passive"))
    )
    (net (code "64") (name "Net-(D15-K)") (class "Default")
      (node (ref "D15") (pin "2") (pinfunction "K_2") (pintype "passive"))
      (node (ref "Q2") (pin "3") (pinfunction "C_3") (pintype "passive"))
      (node (ref "R17") (pin "1") (pinfunction "1_1") (pintype "passive"))
    )
    (net (code "65") (name "Net-(D16-IO1)") (class "Default")
      (node (ref "D16") (pin "1") (pinfunction "IO1_1") (pintype "passive"))
      (node (ref "R24") (pin "2") (pinfunction "2_2") (pintype "passive"))
      (node (ref "USB") (pin "2") (pinfunction "D-_2") (pintype "passive"))
    )
    (net (code "66") (name "Net-(D16-IO2)") (class "Default")
      (node (ref "D16") (pin "2") (pinfunction "IO2_2") (pintype "passive"))
      (node (ref "R28") (pin "2") (pinfunction "2_2") (pintype "passive"))
      (node (ref "USB") (pin "3") (pinfunction "D+_3") (pintype "passive"))
    )
    (net (code "67") (name "Net-(P3-Pad3)") (class "Default")
      (node (ref "P3") (pin "3") (pinfunction "3_3") (pintype "passive"))
      (node (ref "R14") (pin "1") (pinfunction "1_1") (pintype "passive"))
    )
    (net (code "68") (name "Net-(P3-Pad4)") (class "Default")
      (node (ref "P3") (pin "4") (pinfunction "4_4") (pintype "passive"))
      (node (ref "R16") (pin "1") (pinfunction "1_1") (pintype "passive"))
    )
    (net (code "69") (name "Net-(Q2-B)") (class "Default")
      (node (ref "Q2") (pin "1") (pinfunction "B_1") (pintype "passive"))
      (node (ref "R23") (pin "2") (pinfunction "2_2") (pintype "passive"))
    )
    (net (code "70") (name "Net-(Q2-E)") (class "Default")
      (node (ref "Q2") (pin "2") (pinfunction "E_2") (pintype "passive"))
      (node (ref "R27") (pin "1") (pinfunction "1_1") (pintype "passive"))
      (node (ref "U8") (pin "14") (pinfunction "RTS#_14") (pintype "passive"))
    )
    (net (code "71") (name "Net-(Q3-B)") (class "Default")
      (node (ref "Q3") (pin "1") (pinfunction "B_1") (pintype "passive"))
      (node (ref "R27") (pin "2") (pinfunction "2_2") (pintype "passive"))
    )
    (net (code "72") (name "Net-(U1-PD0_OSC_IN)") (class "Default")
      (node (ref "U1") (pin "5") (pinfunction "PD0_OSC_IN_5") (pintype "passive"))
      (node (ref "Y1") (pin "1") (pinfunction "1_1") (pintype "passive"))
    )
    (net (code "73") (name "Net-(U1-PD1_OSC_OUT)") (class "Default")
      (node (ref "U1") (pin "6") (pinfunction "PD1_OSC_OUT_6") (pintype "passive"))
      (node (ref "Y1") (pin "2") (pinfunction "2_2") (pintype "passive"))
    )
    (net (code "74") (name "Net-(U3-*CS)") (class "Default")
      (node (ref "R4") (pin "1") (pinfunction "1_1") (pintype "passive"))
      (node (ref "U3") (pin "7") (pinfunction "*CS_7") (pintype "passive"))
    )
    (net (code "75") (name "Net-(U5-WP)") (class "Default")
      (node (ref "R15") (pin "1") (pinfunction "1_1") (pintype "passive"))
      (node (ref "U5") (pin "7") (pinfunction "WP_7") (pintype "passive"))
    )
    (net (code "76") (name "Net-(U6-PROG)") (class "Default")
      (node (ref "R29") (pin "1") (pinfunction "1_1") (pintype "passive"))
      (node (ref "U6") (pin "6") (pinfunction "PROG_6") (pintype "passive"))
    )
    (net (code "77") (name "Net-(U6-STAT1)") (class "Default")
      (node (ref "R20") (pin "1") (pinfunction "1_1") (pintype "passive"))
      (node (ref "U6") (pin "3") (pinfunction "STAT1_3") (pintype "passive"))
    )
    (net (code "78") (name "Net-(U6-STAT2)") (class "Default")
      (node (ref "R22") (pin "1") (pinfunction "1_1") (pintype "passive"))
      (node (ref "U6") (pin "4") (pinfunction "STAT2_4") (pintype "passive"))
    )
    (net (code "79") (name "Net-(U6-THERM)") (class "Default")
      (node (ref "R25") (pin "1") (pinfunction "1_1") (pintype "passive"))
      (node (ref "U6") (pin "8") (pinfunction "THERM_8") (pintype "passive"))
    )
    (net (code "80") (name "Net-(U7-EN)") (class "Default")
      (node (ref "R21") (pin "1") (pinfunction "1_1") (pintype "passive"))
      (node (ref "U7") (pin "3") (pinfunction "EN_3") (pintype "passive"))
    )
    (net (code "81") (name "Net-(U8-3V)") (class "Default")
      (node (ref "C17") (pin "2") (pinfunction "2_2") (pintype "passive"))
      (node (ref "U8") (pin "4") (pinfunction "3V_4") (pintype "passive"))
    )
    (net (code "82") (name "Net-(U8-DTR#)") (class "Default")
      (node (ref "R23") (pin "1") (pinfunction "1_1") (pintype "passive"))
      (node (ref "U8") (pin "13") (pinfunction "DTR#_13") (pintype "passive"))
    )
    (net (code "83") (name "Net-(U8-RXD)") (class "Default")
      (node (ref "R19") (pin "1") (pinfunction "1_1") (pintype "passive"))
      (node (ref "U8") (pin "3") (pinfunction "RXD_3") (pintype "passive"))
    )
    (net (code "84") (name "Net-(U8-TXD)") (class "Default")
      (node (ref "R18") (pin "1") (pinfunction "1_1") (pintype "passive"))
      (node (ref "U8") (pin "2") (pinfunction "TXD_2") (pintype "passive"))
    )
    (net (code "85") (name "VBAT") (class "Default")
      (node (ref "C18") (pin "1") (pinfunction "1_1") (pintype "passive"))
      (node (ref "D10") (pin "1") (pinfunction "A_1") (pintype "passive"))
      (node (ref "P2") (pin "2") (pinfunction "2_2") (pintype "passive"))
      (node (ref "Q1") (pin "3") (pinfunction "D_3") (pintype "passive"))
      (node (ref "TP2") (pin "1") (pinfunction "1_1") (pintype "passive"))
      (node (ref "U6") (pin "10") (pinfunction "VBAT_10") (pintype "passive"))
      (node (ref "U6") (pin "9") (pinfunction "VBAT_9") (pintype "passive"))
    )
    (net (code "86") (name "VUSB") (class "Default")
      (node (ref "D11") (pin "1") (pinfunction "A_1") (pintype "passive"))
      (node (ref "USB") (pin "1") (pinfunction "VCC_1") (pintype "passive"))
    )
    (net (code "87") (name "V_RTC") (class "Default")
      (node (ref "BAT") (pin "1") (pinfunction "+3V_1") (pintype "passive"))
      (node (ref "C7") (pin "2") (pinfunction "2_2") (pintype "passive"))
      (node (ref "C8") (pin "2") (pinfunction "2_2") (pintype "passive"))
      (node (ref "U1") (pin "1") (pinfunction "VBAT_1") (pintype "passive"))
    )
    (net (code "88") (name "unconnected-(BLD-Pad3)") (class "Default")
      (node (ref "BLD") (pin "3") (pintype "passive"))
    )
    (net (code "89") (name "unconnected-(BLD-Pad4)") (class "Default")
      (node (ref "BLD") (pin "4") (pintype "passive"))
    )
    (net (code "90") (name "unconnected-(RESET-Pad3)") (class "Default")
      (node (ref "RESET") (pin "3") (pintype "passive"))
    )
    (net (code "91") (name "unconnected-(RESET-Pad4)") (class "Default")
      (node (ref "RESET") (pin "4") (pintype "passive"))
    )
    (net (code "92") (name "unconnected-(U1-PA15{slash}SPI3_NSS-Pad50)") (class "Default")
      (node (ref "U1") (pin "50") (pinfunction "PA15/SPI3_NSS_50") (pintype "passive"))
    )
    (net (code "93") (name "unconnected-(U1-PB1-Pad27)") (class "Default")
      (node (ref "U1") (pin "27") (pinfunction "PB1_27") (pintype "passive"))
    )
    (net (code "94") (name "unconnected-(U1-PB9-Pad62)") (class "Default")
      (node (ref "U1") (pin "62") (pinfunction "PB9_62") (pintype "passive"))
    )
    (net (code "95") (name "unconnected-(U1-PB15{slash}SPI2_MOSI-Pad36)") (class "Default")
      (node (ref "U1") (pin "36") (pinfunction "PB15/SPI2_MOSI_36") (pintype "passive"))
    )
    (net (code "96") (name "unconnected-(U1-PC4-Pad24)") (class "Default")
      (node (ref "U1") (pin "24") (pinfunction "PC4_24") (pintype "passive"))
    )
    (net (code "97") (name "unconnected-(U1-PC5-Pad25)") (class "Default")
      (node (ref "U1") (pin "25") (pinfunction "PC5_25") (pintype "passive"))
    )
    (net (code "98") (name "unconnected-(U1-PC6-Pad37)") (class "Default")
      (node (ref "U1") (pin "37") (pinfunction "PC6_37") (pintype "passive"))
    )
    (net (code "99") (name "unconnected-(U1-PC7-Pad38)") (class "Default")
      (node (ref "U1") (pin "38") (pinfunction "PC7_38") (pintype "passive"))
    )
    (net (code "100") (name "unconnected-(U1-PC10{slash}USART4_TX-Pad51)") (class "Default")
      (node (ref "U1") (pin "51") (pinfunction "PC10/USART4_TX_51") (pintype "passive"))
    )
    (net (code "101") (name "unconnected-(U1-PC11_USART4_RX-Pad52)") (class "Default")
      (node (ref "U1") (pin "52") (pinfunction "PC11_USART4_RX_52") (pintype "passive"))
    )
    (net (code "102") (name "unconnected-(U1-PC12{slash}USART5_TX-Pad53)") (class "Default")
      (node (ref "U1") (pin "53") (pinfunction "PC12/USART5_TX_53") (pintype "passive"))
    )
    (net (code "103") (name "unconnected-(U1-PC13-TAMPER-RTC-Pad2)") (class "Default")
      (node (ref "U1") (pin "2") (pinfunction "PC13-TAMPER-RTC_2") (pintype "passive"))
    )
    (net (code "104") (name "unconnected-(U1-PD2{slash}USART5_RX-Pad54)") (class "Default")
      (node (ref "U1") (pin "54") (pinfunction "PD2/USART5_RX_54") (pintype "passive"))
    )
    (net (code "105") (name "unconnected-(U2-GPIO4{slash}EXTPA-Pad11)") (class "Default")
      (node (ref "U2") (pin "11") (pinfunction "GPIO4/EXTPA_11") (pintype "bidirectional"))
    )
    (net (code "106") (name "unconnected-(U2-GPIO5{slash}EXTTXE{slash}SPIPOL-Pad10)") (class "Default")
      (node (ref "U2") (pin "10") (pinfunction "GPIO5/EXTTXE/SPIPOL_10") (pintype "bidirectional"))
    )
    (net (code "107") (name "unconnected-(U2-GPIO6{slash}EXTRXE{slash}SPIPHA-Pad9)") (class "Default")
      (node (ref "U2") (pin "9") (pinfunction "GPIO6/EXTRXE/SPIPHA_9") (pintype "bidirectional"))
    )
    (net (code "108") (name "unconnected-(U2-GPIO7-Pad4)") (class "Default")
      (node (ref "U2") (pin "4") (pinfunction "GPIO7_4") (pintype "input"))
    )
    (net (code "109") (name "unconnected-(U3-NC-Pad10)") (class "Default")
      (node (ref "U3") (pin "10") (pinfunction "NC_10") (pintype "passive"))
    )
    (net (code "110") (name "unconnected-(U3-RESERVED-Pad3)") (class "Default")
      (node (ref "U3") (pin "3") (pinfunction "RESERVED_3") (pintype "passive"))
    )
    (net (code "111") (name "unconnected-(U3-RESERVED-Pad11)") (class "Default")
      (node (ref "U3") (pin "11") (pinfunction "RESERVED_11") (pintype "passive"))
    )
    (net (code "112") (name "unconnected-(U6-*PG-Pad7)") (class "Default")
      (node (ref "U6") (pin "7") (pinfunction "*PG_7") (pintype "passive"))
    )
    (net (code "113") (name "unconnected-(U6-EP-Pad11)") (class "Default")
      (node (ref "U6") (pin "11") (pinfunction "EP_11") (pintype "passive"))
    )
    (net (code "114") (name "unconnected-(U7-NC-Pad4)") (class "Default")
      (node (ref "U7") (pin "4") (pinfunction "NC_4") (pintype "passive"))
    )
    (net (code "115") (name "unconnected-(U8-CTR#-Pad9)") (class "Default")
      (node (ref "U8") (pin "9") (pinfunction "CTR#_9") (pintype "passive"))
    )
    (net (code "116") (name "unconnected-(U8-DCD#-Pad12)") (class "Default")
      (node (ref "U8") (pin "12") (pinfunction "DCD#_12") (pintype "passive"))
    )
    (net (code "117") (name "unconnected-(U8-DSR#-Pad10)") (class "Default")
      (node (ref "U8") (pin "10") (pinfunction "DSR#_10") (pintype "passive"))
    )
    (net (code "118") (name "unconnected-(U8-NC-Pad7)") (class "Default")
      (node (ref "U8") (pin "7") (pinfunction "NC_7") (pintype "passive"))
    )
    (net (code "119") (name "unconnected-(U8-NC-Pad8)") (class "Default")
      (node (ref "U8") (pin "8") (pinfunction "NC_8") (pintype "passive"))
    )
    (net (code "120") (name "unconnected-(U8-RI#-Pad11)") (class "Default")
      (node (ref "U8") (pin "11") (pinfunction "RI#_11") (pintype "passive"))
    )
    (net (code "121") (name "unconnected-(U8-RS232-Pad15)") (class "Default")
      (node (ref "U8") (pin "15") (pinfunction "RS232_15") (pintype "passive"))
    )
    (net (code "122") (name "unconnected-(USB-ID-Pad4)") (class "Default")
      (node (ref "USB") (pin "4") (pinfunction "ID_4") (pintype "passive"))
    )
  )
)
